# 6_din.net
KiCad netlist of a schematic drawn in Altium Designer
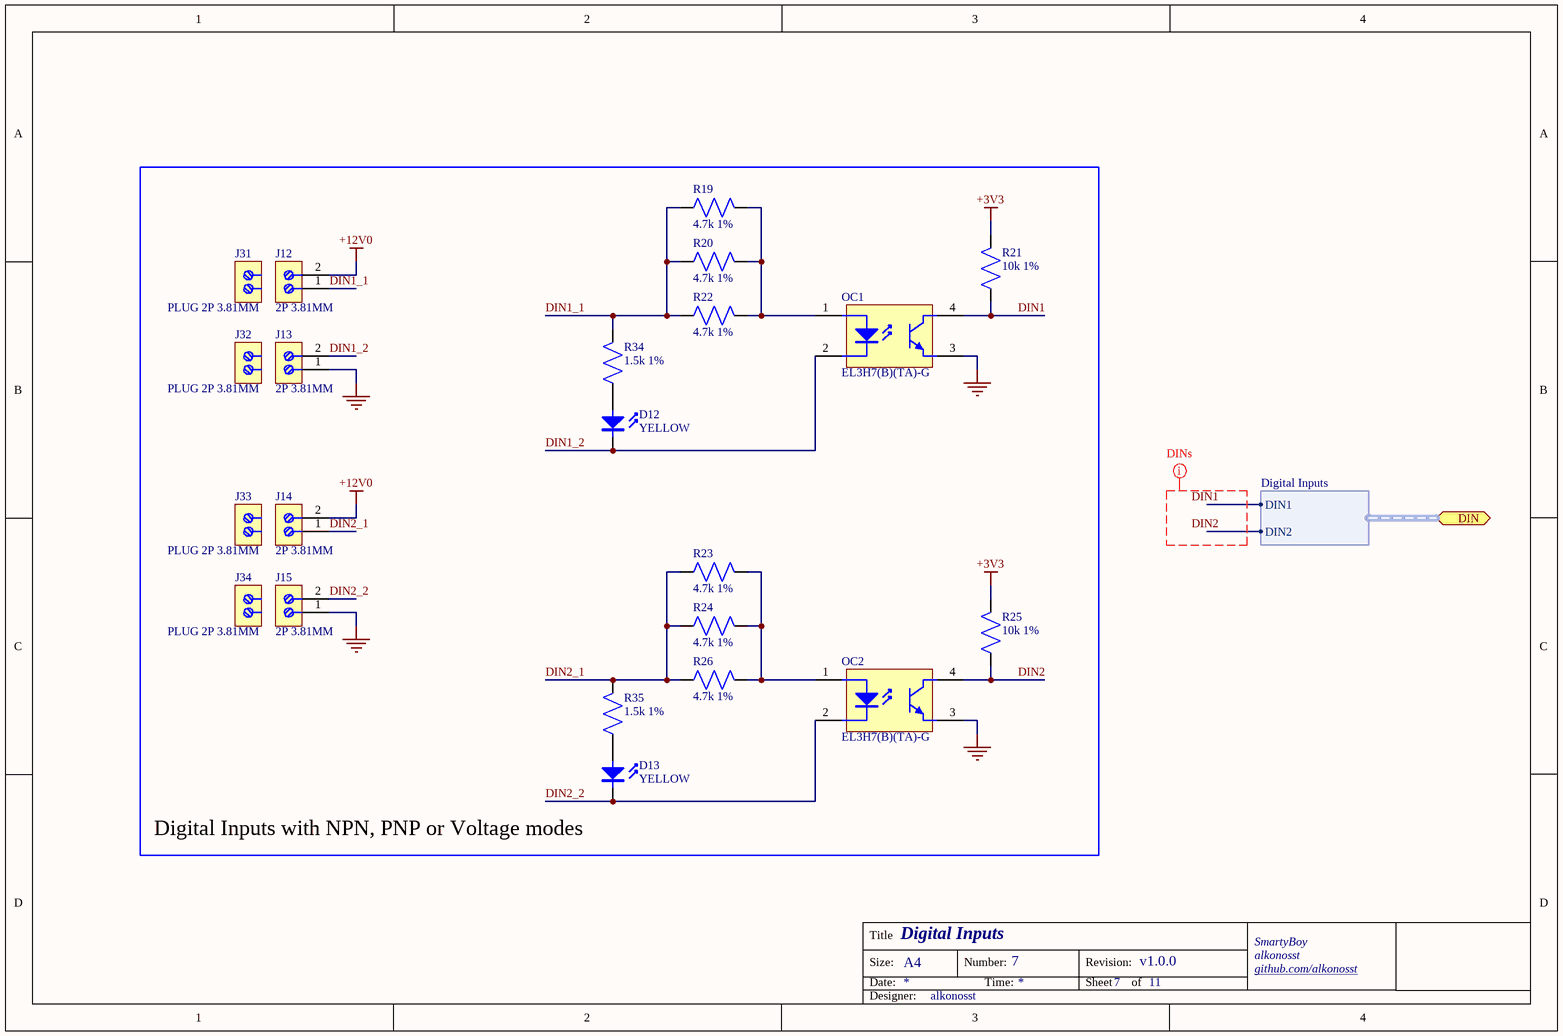
[diagram p0: 6_din.SchDoc]

(export (version "E")
  (design (tool "Eeschema 10.0.6"))
  (components
    (comp (ref "D12")
      (value "YELLOW")
      (footprint "LED0603-YELLOW")
      (description "Yellow 585.5~591.5nm 0603 Light Emitting Diodes (LED)")
      (fields (field (name "LCSC PART") "C72038"))
      (libsource (lib "nombre_por_definir") (part "19-213/Y2C-CQ2R2L/3T(CY)"))
    )
    (comp (ref "D13")
      (value "YELLOW")
      (footprint "LED0603-YELLOW")
      (description "Yellow 585.5~591.5nm 0603 Light Emitting Diodes (LED)")
      (fields (field (name "LCSC PART") "C72038"))
      (libsource (lib "nombre_por_definir") (part "19-213/Y2C-CQ2R2L/3T(CY)"))
    )
    (comp (ref "J12")
      (value "2P 3.81MM")
      (footprint "TB-2P-3.81MM")
      (description "Terminal Block 2 Positions 3.81MM")
      (libsource (lib "nombre_por_definir") (part "TBLOCK-2P-3.81MM"))
    )
    (comp (ref "J13")
      (value "2P 3.81MM")
      (footprint "TB-2P-3.81MM")
      (description "Terminal Block 2 Positions 3.81MM")
      (libsource (lib "nombre_por_definir") (part "TBLOCK-2P-3.81MM"))
    )
    (comp (ref "J14")
      (value "2P 3.81MM")
      (footprint "TB-2P-3.81MM")
      (description "Terminal Block 2 Positions 3.81MM")
      (libsource (lib "nombre_por_definir") (part "TBLOCK-2P-3.81MM"))
    )
    (comp (ref "J15")
      (value "2P 3.81MM")
      (footprint "TB-2P-3.81MM")
      (description "Terminal Block 2 Positions 3.81MM")
      (libsource (lib "nombre_por_definir") (part "TBLOCK-2P-3.81MM"))
    )
    (comp (ref "J31")
      (value "PLUG 2P 3.81MM")
      (footprint "TB-PLUG-2P-3.81MM")
      (description "Terminal block plug 2positions 3.81mm")
      (libsource (lib "nombre_por_definir") (part "PLUG-2P-3.81MM"))
    )
    (comp (ref "J32")
      (value "PLUG 2P 3.81MM")
      (footprint "TB-PLUG-2P-3.81MM")
      (description "Terminal block plug 2positions 3.81mm")
      (libsource (lib "nombre_por_definir") (part "PLUG-2P-3.81MM"))
    )
    (comp (ref "J33")
      (value "PLUG 2P 3.81MM")
      (footprint "TB-PLUG-2P-3.81MM")
      (description "Terminal block plug 2positions 3.81mm")
      (libsource (lib "nombre_por_definir") (part "PLUG-2P-3.81MM"))
    )
    (comp (ref "J34")
      (value "PLUG 2P 3.81MM")
      (footprint "TB-PLUG-2P-3.81MM")
      (description "Terminal block plug 2positions 3.81mm")
      (libsource (lib "nombre_por_definir") (part "PLUG-2P-3.81MM"))
    )
    (comp (ref "OC1")
      (value "EL3H7(B)(TA)-G")
      (footprint "SSOP-4")
      (description "1 3750Vrms TransistorOptocouplers DC SOP-4_P1.27 Optocouplers - Phototransistor Output")
      (fields (field (name "LCSC PART") "C32565"))
      (libsource (lib "nombre_por_definir") (part "EL3H7(B)(TA)-G"))
    )
    (comp (ref "OC2")
      (value "EL3H7(B)(TA)-G")
      (footprint "SSOP-4")
      (description "1 3750Vrms TransistorOptocouplers DC SOP-4_P1.27 Optocouplers - Phototransistor Output")
      (fields (field (name "LCSC PART") "C32565"))
      (libsource (lib "nombre_por_definir") (part "EL3H7(B)(TA)-G"))
    )
    (comp (ref "R19")
      (value "4.7k 1%")
      (footprint "R1206")
      (description "0.25W ±1% 4.7kΩ ±100ppm/℃ 1206 Chip Resistor - Surface Mount")
      (fields (field (name "LCSC PART") "C17936"))
      (libsource (lib "nombre_por_definir") (part "1206W4F4701T5E"))
    )
    (comp (ref "R20")
      (value "4.7k 1%")
      (footprint "R1206")
      (description "0.25W ±1% 4.7kΩ ±100ppm/℃ 1206 Chip Resistor - Surface Mount")
      (fields (field (name "LCSC PART") "C17936"))
      (libsource (lib "nombre_por_definir") (part "1206W4F4701T5E"))
    )
    (comp (ref "R21")
      (value "10k 1%")
      (footprint "R0603")
      (description "±1% ±100ppm/℃ 10kΩ 0.1W 0603 Chip Resistor - Surface Mount")
      (fields (field (name "LCSC PART") "C25804"))
      (libsource (lib "nombre_por_definir") (part "0603WAF1002T5E"))
    )
    (comp (ref "R22")
      (value "4.7k 1%")
      (footprint "R1206")
      (description "0.25W ±1% 4.7kΩ ±100ppm/℃ 1206 Chip Resistor - Surface Mount")
      (fields (field (name "LCSC PART") "C17936"))
      (libsource (lib "nombre_por_definir") (part "1206W4F4701T5E"))
    )
    (comp (ref "R23")
      (value "4.7k 1%")
      (footprint "R1206")
      (description "0.25W ±1% 4.7kΩ ±100ppm/℃ 1206 Chip Resistor - Surface Mount")
      (fields (field (name "LCSC PART") "C17936"))
      (libsource (lib "nombre_por_definir") (part "1206W4F4701T5E"))
    )
    (comp (ref "R24")
      (value "4.7k 1%")
      (footprint "R1206")
      (description "0.25W ±1% 4.7kΩ ±100ppm/℃ 1206 Chip Resistor - Surface Mount")
      (fields (field (name "LCSC PART") "C17936"))
      (libsource (lib "nombre_por_definir") (part "1206W4F4701T5E"))
    )
    (comp (ref "R25")
      (value "10k 1%")
      (footprint "R0603")
      (description "±1% ±100ppm/℃ 10kΩ 0.1W 0603 Chip Resistor - Surface Mount")
      (fields (field (name "LCSC PART") "C25804"))
      (libsource (lib "nombre_por_definir") (part "0603WAF1002T5E"))
    )
    (comp (ref "R26")
      (value "4.7k 1%")
      (footprint "R1206")
      (description "0.25W ±1% 4.7kΩ ±100ppm/℃ 1206 Chip Resistor - Surface Mount")
      (fields (field (name "LCSC PART") "C17936"))
      (libsource (lib "nombre_por_definir") (part "1206W4F4701T5E"))
    )
    (comp (ref "R34")
      (value "1.5k 1%")
      (footprint "R0603")
      (description "1.5kΩ ±1% ±100ppm/℃ 0.1W 0603 Chip Resistor - Surface Mount")
      (fields (field (name "LCSC PART") "C22843"))
      (libsource (lib "nombre_por_definir") (part "0603WAF1501T5E"))
    )
    (comp (ref "R35")
      (value "1.5k 1%")
      (footprint "R0603")
      (description "1.5kΩ ±1% ±100ppm/℃ 0.1W 0603 Chip Resistor - Surface Mount")
      (fields (field (name "LCSC PART") "C22843"))
      (libsource (lib "nombre_por_definir") (part "0603WAF1501T5E"))
    )
  )
  (nets
    (net (code "3") (name "+3V3") (class "Default")
      (node (ref "R21") (pin "2") (pinfunction "2_2") (pintype "passive"))
      (node (ref "R25") (pin "2") (pinfunction "2_2") (pintype "passive"))
    )
    (net (code "4") (name "+12V0") (class "Default")
      (node (ref "J12") (pin "2") (pinfunction "2_2") (pintype "passive"))
      (node (ref "J14") (pin "2") (pinfunction "2_2") (pintype "passive"))
    )
    (net (code "5") (name "/DIN1") (class "Default")
      (node (ref "OC1") (pin "4") (pinfunction "C_4") (pintype "passive"))
      (node (ref "R21") (pin "1") (pinfunction "1_1") (pintype "passive"))
    )
    (net (code "6") (name "/DIN1_1") (class "Default")
      (node (ref "J12") (pin "1") (pinfunction "1_1") (pintype "passive"))
      (node (ref "R19") (pin "1") (pinfunction "1_1") (pintype "passive"))
      (node (ref "R20") (pin "1") (pinfunction "1_1") (pintype "passive"))
      (node (ref "R22") (pin "1") (pinfunction "1_1") (pintype "passive"))
      (node (ref "R34") (pin "2") (pinfunction "2_2") (pintype "passive"))
    )
    (net (code "7") (name "/DIN1_2") (class "Default")
      (node (ref "D12") (pin "1") (pinfunction "1_1") (pintype "passive"))
      (node (ref "J13") (pin "2") (pinfunction "2_2") (pintype "passive"))
      (node (ref "OC1") (pin "2") (pinfunction "K_2") (pintype "passive"))
    )
    (net (code "8") (name "/DIN2") (class "Default")
      (node (ref "OC2") (pin "4") (pinfunction "C_4") (pintype "passive"))
      (node (ref "R25") (pin "1") (pinfunction "1_1") (pintype "passive"))
    )
    (net (code "9") (name "/DIN2_1") (class "Default")
      (node (ref "J14") (pin "1") (pinfunction "1_1") (pintype "passive"))
      (node (ref "R23") (pin "1") (pinfunction "1_1") (pintype "passive"))
      (node (ref "R24") (pin "1") (pinfunction "1_1") (pintype "passive"))
      (node (ref "R26") (pin "1") (pinfunction "1_1") (pintype "passive"))
      (node (ref "R35") (pin "2") (pinfunction "2_2") (pintype "passive"))
    )
    (net (code "10") (name "/DIN2_2") (class "Default")
      (node (ref "D13") (pin "1") (pinfunction "1_1") (pintype "passive"))
      (node (ref "J15") (pin "2") (pinfunction "2_2") (pintype "passive"))
      (node (ref "OC2") (pin "2") (pinfunction "K_2") (pintype "passive"))
    )
    (net (code "12") (name "GND") (class "Default")
      (node (ref "J13") (pin "1") (pinfunction "1_1") (pintype "passive"))
      (node (ref "J15") (pin "1") (pinfunction "1_1") (pintype "passive"))
      (node (ref "OC1") (pin "3") (pinfunction "E_3") (pintype "passive"))
      (node (ref "OC2") (pin "3") (pinfunction "E_3") (pintype "passive"))
    )
    (net (code "13") (name "Net-(D12-Pad2)") (class "Default")
      (node (ref "D12") (pin "2") (pinfunction "2_2") (pintype "passive"))
      (node (ref "R34") (pin "1") (pinfunction "1_1") (pintype "passive"))
    )
    (net (code "14") (name "Net-(D13-Pad2)") (class "Default")
      (node (ref "D13") (pin "2") (pinfunction "2_2") (pintype "passive"))
      (node (ref "R35") (pin "1") (pinfunction "1_1") (pintype "passive"))
    )
    (net (code "15") (name "Net-(OC1-A)") (class "Default")
      (node (ref "OC1") (pin "1") (pinfunction "A_1") (pintype "passive"))
      (node (ref "R19") (pin "2") (pinfunction "2_2") (pintype "passive"))
      (node (ref "R20") (pin "2") (pinfunction "2_2") (pintype "passive"))
      (node (ref "R22") (pin "2") (pinfunction "2_2") (pintype "passive"))
    )
    (net (code "16") (name "Net-(OC2-A)") (class "Default")
      (node (ref "OC2") (pin "1") (pinfunction "A_1") (pintype "passive"))
      (node (ref "R23") (pin "2") (pinfunction "2_2") (pintype "passive"))
      (node (ref "R24") (pin "2") (pinfunction "2_2") (pintype "passive"))
      (node (ref "R26") (pin "2") (pinfunction "2_2") (pintype "passive"))
    )
  )
)
